# Z7_BLOCK.net
KiCad netlist of a schematic drawn in Altium Designer
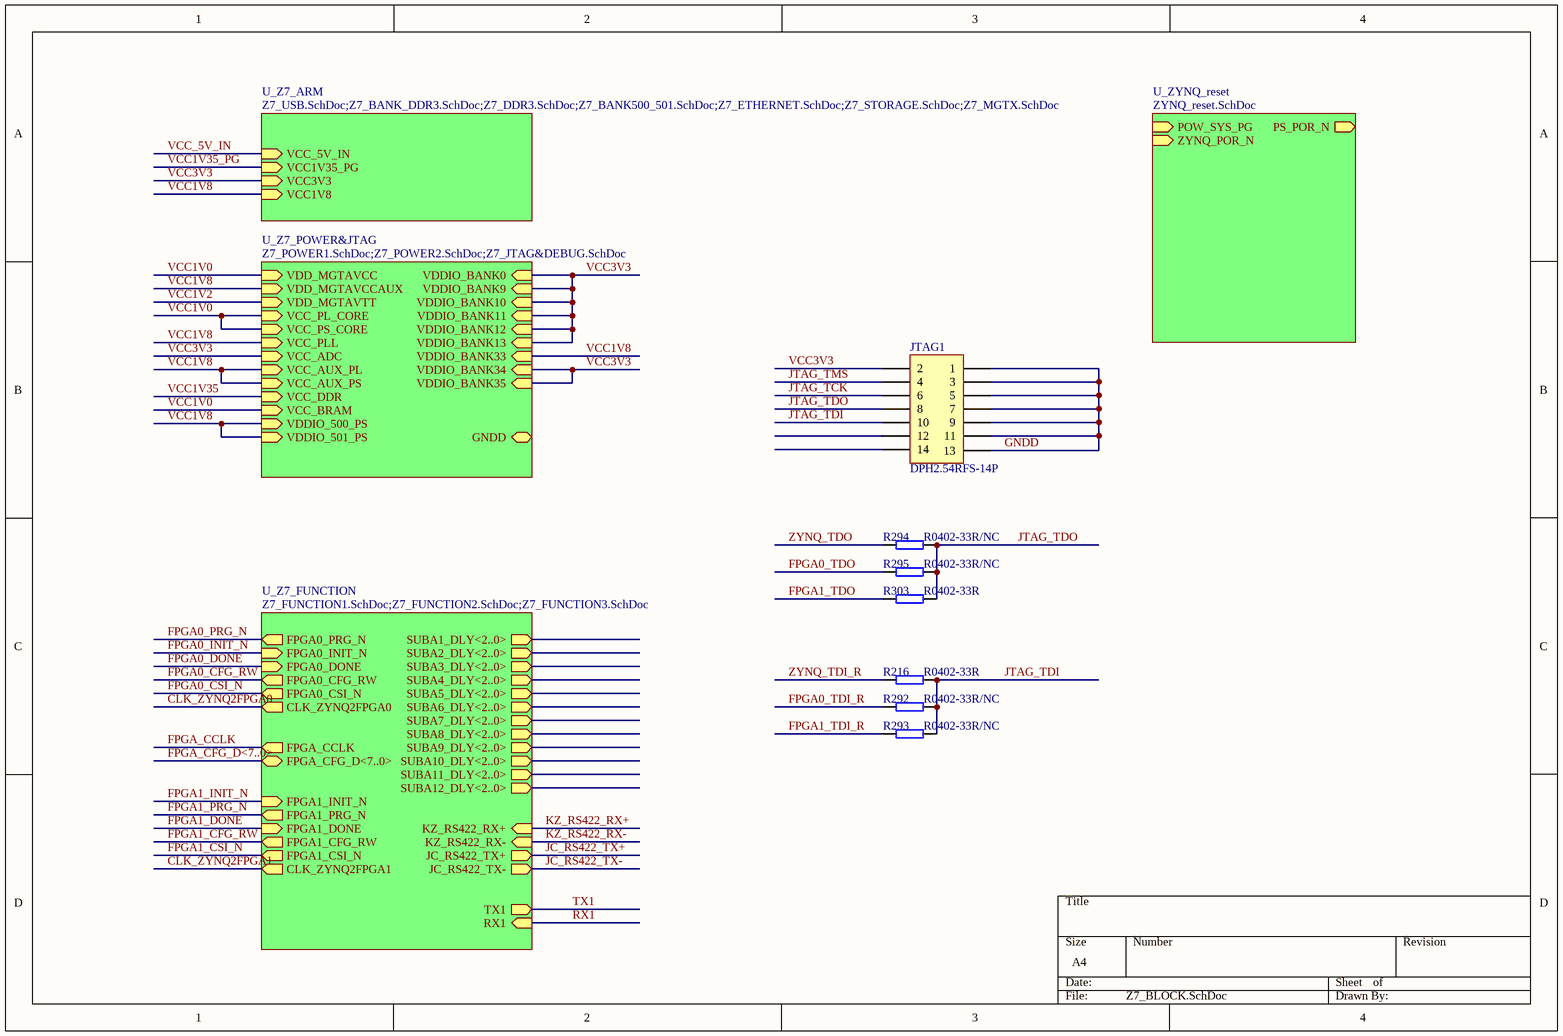
[diagram p0: Z7_BLOCK.SchDoc]

(export (version "E")
  (design (tool "Eeschema 10.0.6"))
  (components
    (comp (ref "JTAG1")
      (value "DPH2.54RFS-14P")
      (footprint "IDC2.54-14")
      (description "2.54间距14芯双排插针")
      (libsource (lib "Schlib1") (part "DPH2.54RFS-14P"))
    )
    (comp (ref "R216")
      (value "R0402-33R")
      (footprint "R0402")
      (fields (field (name "SCHEMATIC_PART") "RES") (field (name "MANUFACTURER") "SAMSUNG"))
      (libsource (lib "Database_Libs1") (part "RES"))
    )
    (comp (ref "R292")
      (value "R0402-33R/NC")
      (footprint "R0402")
      (fields (field (name "SCHEMATIC_PART") "RES") (field (name "MANUFACTURER") "SAMSUNG"))
      (libsource (lib "Database_Libs1") (part "RES"))
    )
    (comp (ref "R293")
      (value "R0402-33R/NC")
      (footprint "R0402")
      (fields (field (name "SCHEMATIC_PART") "RES") (field (name "MANUFACTURER") "SAMSUNG"))
      (libsource (lib "Database_Libs1") (part "RES"))
    )
    (comp (ref "R294")
      (value "R0402-33R/NC")
      (footprint "R0402")
      (fields (field (name "SCHEMATIC_PART") "RES") (field (name "MANUFACTURER") "SAMSUNG"))
      (libsource (lib "Database_Libs1") (part "RES"))
    )
    (comp (ref "R295")
      (value "R0402-33R/NC")
      (footprint "R0402")
      (fields (field (name "SCHEMATIC_PART") "RES") (field (name "MANUFACTURER") "SAMSUNG"))
      (libsource (lib "Database_Libs1") (part "RES"))
    )
    (comp (ref "R303")
      (value "R0402-33R")
      (footprint "R0402")
      (fields (field (name "SCHEMATIC_PART") "RES") (field (name "MANUFACTURER") "SAMSUNG"))
      (libsource (lib "Database_Libs1") (part "RES"))
    )
  )
  (nets
    (net (code "9") (name "/FPGA0_TDI_R") (class "Default") (node (ref "R292") (pin "1") (pintype "passive")))
    (net (code "10") (name "/FPGA0_TDO") (class "Default") (node (ref "R295") (pin "1") (pintype "passive")))
    (net (code "16") (name "/FPGA1_TDI_R") (class "Default")
      (node (ref "R293") (pin "1") (pintype "passive"))
    )
    (net (code "17") (name "/FPGA1_TDO") (class "Default") (node (ref "R303") (pin "1") (pintype "passive")))
    (net (code "19") (name "/GNDD") (class "Default")
      (node (ref "JTAG1") (pin "1") (pinfunction "1_1") (pintype "passive"))
      (node (ref "JTAG1") (pin "11") (pinfunction "11_11") (pintype "passive"))
      (node (ref "JTAG1") (pin "13") (pinfunction "13_13") (pintype "passive"))
      (node (ref "JTAG1") (pin "3") (pinfunction "3_3") (pintype "passive"))
      (node (ref "JTAG1") (pin "5") (pinfunction "5_5") (pintype "passive"))
      (node (ref "JTAG1") (pin "7") (pinfunction "7_7") (pintype "passive"))
      (node (ref "JTAG1") (pin "9") (pinfunction "9_9") (pintype "passive"))
    )
    (net (code "23") (name "/JTAG_TCK") (class "Default")
      (node (ref "JTAG1") (pin "6") (pinfunction "6_6") (pintype "passive"))
    )
    (net (code "24") (name "/JTAG_TDI") (class "Default")
      (node (ref "JTAG1") (pin "10") (pinfunction "10_10") (pintype "passive"))
      (node (ref "R216") (pin "2") (pintype "passive"))
      (node (ref "R292") (pin "2") (pintype "passive"))
      (node (ref "R293") (pin "2") (pintype "passive"))
    )
    (net (code "25") (name "/JTAG_TDO") (class "Default")
      (node (ref "JTAG1") (pin "8") (pinfunction "8_8") (pintype "passive"))
      (node (ref "R294") (pin "2") (pintype "passive"))
      (node (ref "R295") (pin "2") (pintype "passive"))
      (node (ref "R303") (pin "2") (pintype "passive"))
    )
    (net (code "26") (name "/JTAG_TMS") (class "Default")
      (node (ref "JTAG1") (pin "4") (pinfunction "4_4") (pintype "passive"))
    )
    (net (code "50") (name "/VCC3V3") (class "Default")
      (node (ref "JTAG1") (pin "2") (pinfunction "2_2") (pintype "passive"))
    )
    (net (code "53") (name "/ZYNQ_TDI_R") (class "Default") (node (ref "R216") (pin "1") (pintype "passive")))
    (net (code "54") (name "/ZYNQ_TDO") (class "Default") (node (ref "R294") (pin "1") (pintype "passive")))
    (net (code "56") (name "unconnected-(JTAG1-Pad12)") (class "Default")
      (node (ref "JTAG1") (pin "12") (pinfunction "12_12") (pintype "passive"))
    )
    (net (code "57") (name "unconnected-(JTAG1-Pad14)") (class "Default")
      (node (ref "JTAG1") (pin "14") (pinfunction "14_14") (pintype "passive"))
    )
  )
)
